# Esp32_Shield_V3_no_LED.net
KiCad netlist of a schematic drawn in EAGLE
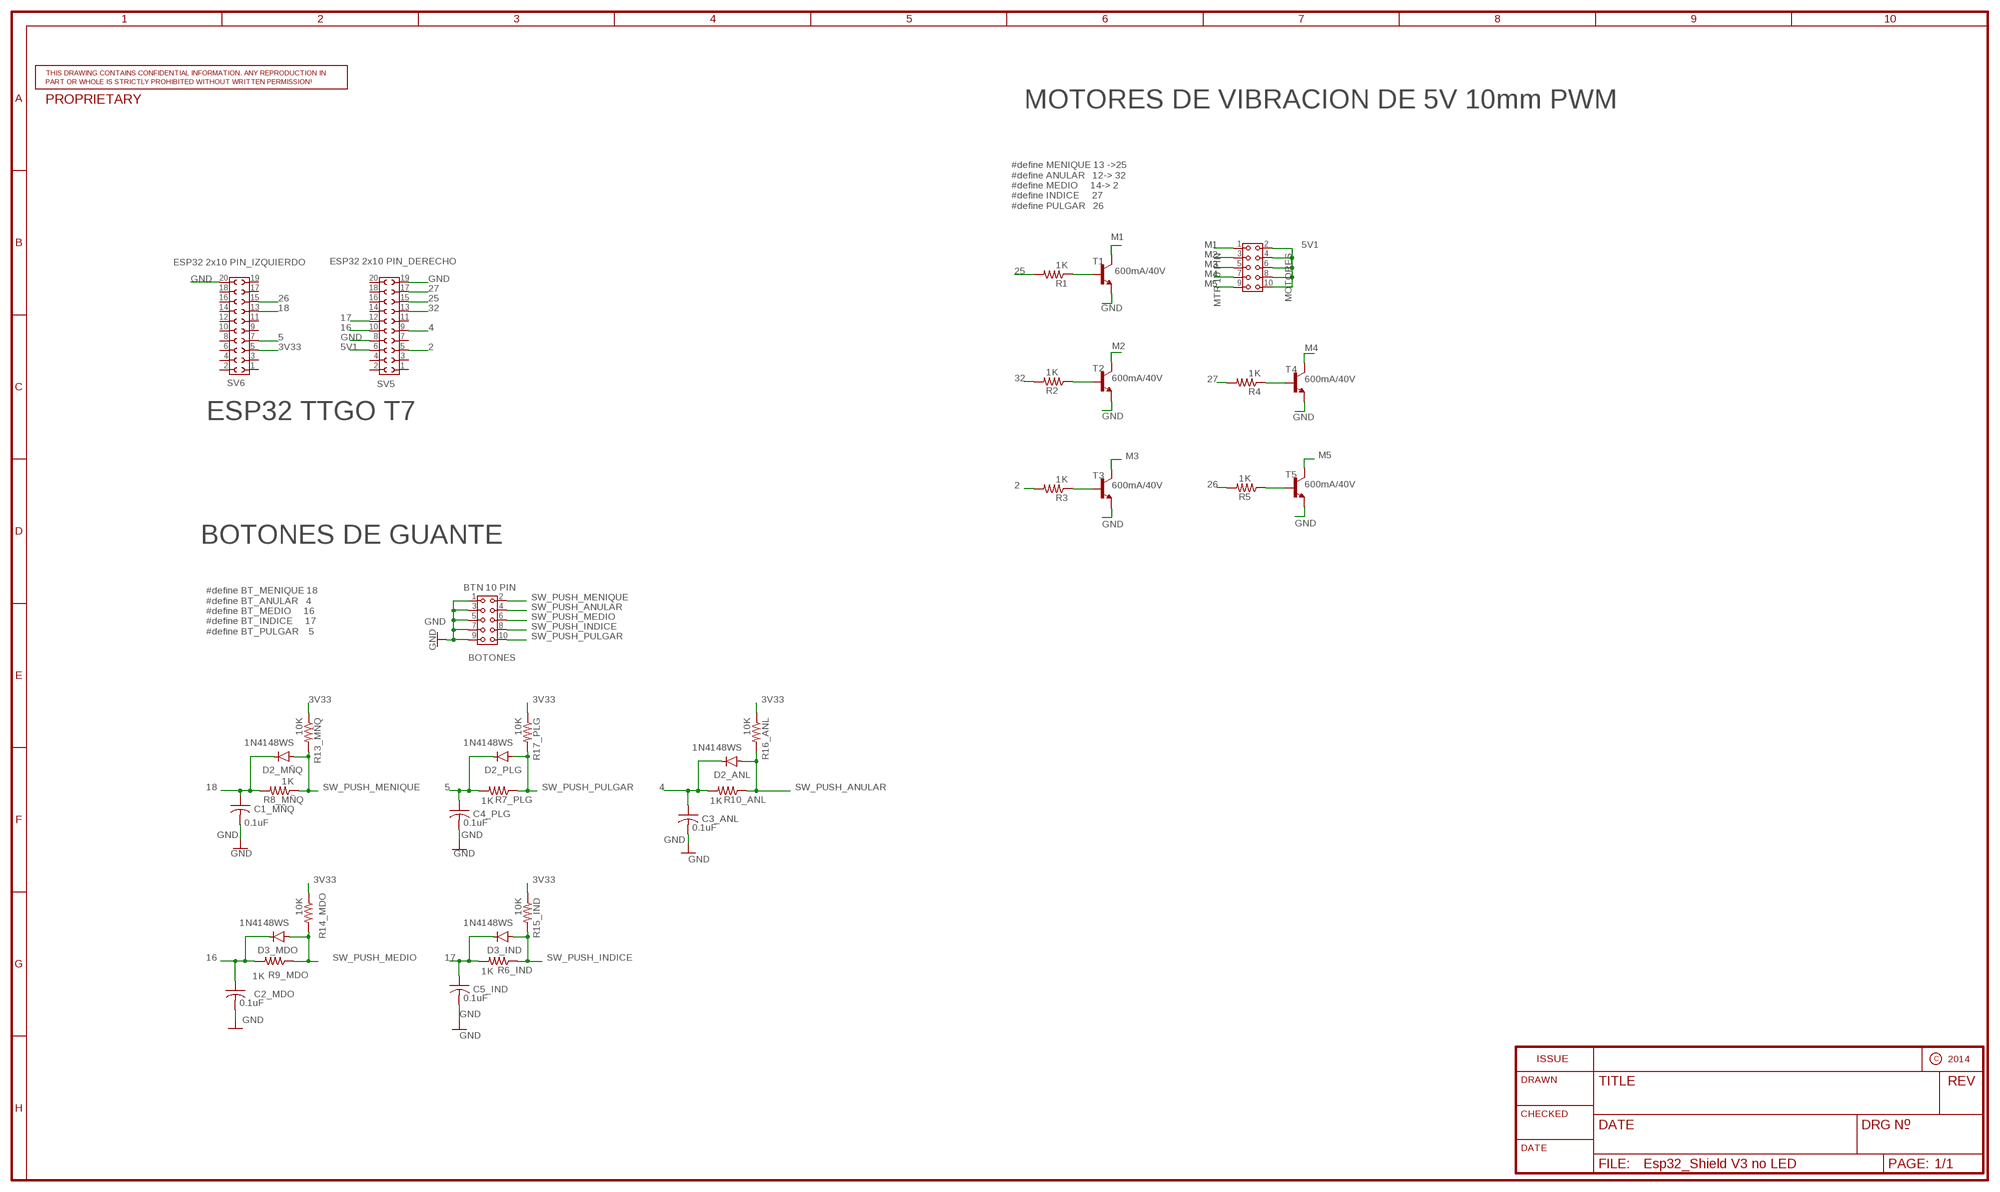
[diagram p0: schematic, sheet 1]

(export (version "E")
  (design (tool "Eeschema 10.0.6"))
  (components
    (comp (ref "BOTONES")
      (value "BTN 10 PIN")
      (footprint "eagle-import:61301021821")
      (libsource (lib "eagle-import") (part "6130XX21821_61301021821"))
    )
    (comp (ref "C1_MÑQ")
      (value "0.1uF")
      (footprint "eagle-import:C0805")
      (libsource (lib "eagle-import") (part "C-USC0805"))
    )
    (comp (ref "C2_MDO")
      (value "0.1uF")
      (footprint "eagle-import:C0805")
      (libsource (lib "eagle-import") (part "C-USC0805"))
    )
    (comp (ref "C3_ANL")
      (value "0.1uF")
      (footprint "eagle-import:C0805")
      (libsource (lib "eagle-import") (part "C-USC0805"))
    )
    (comp (ref "C4_PLG")
      (value "0.1uF")
      (footprint "eagle-import:C0805")
      (libsource (lib "eagle-import") (part "C-USC0805"))
    )
    (comp (ref "C5_IND")
      (value "0.1uF")
      (footprint "eagle-import:C0805")
      (libsource (lib "eagle-import") (part "C-USC0805"))
    )
    (comp (ref "D2_ANL")
      (value "1N4148WS")
      (footprint "eagle-import:SOD-323")
      (fields
        (field (name "DIGIKEY_PART_NUMBER") "1N4148WSFSTR-ND")
        (field (name "MANUFACTURER") "Diodes Incorporated")
        (field (name "CREATED_BY") "PCBLayout.com")
      )
      (libsource (lib "eagle-import") (part "1N4148WS"))
    )
    (comp (ref "D2_MÑQ")
      (value "1N4148WS")
      (footprint "eagle-import:SOD-323")
      (fields
        (field (name "DIGIKEY_PART_NUMBER") "1N4148WSFSTR-ND")
        (field (name "MANUFACTURER") "Diodes Incorporated")
        (field (name "CREATED_BY") "PCBLayout.com")
      )
      (libsource (lib "eagle-import") (part "1N4148WS"))
    )
    (comp (ref "D2_PLG")
      (value "1N4148WS")
      (footprint "eagle-import:SOD-323")
      (fields
        (field (name "DIGIKEY_PART_NUMBER") "1N4148WSFSTR-ND")
        (field (name "MANUFACTURER") "Diodes Incorporated")
        (field (name "CREATED_BY") "PCBLayout.com")
      )
      (libsource (lib "eagle-import") (part "1N4148WS"))
    )
    (comp (ref "D3_IND")
      (value "1N4148WS")
      (footprint "eagle-import:SOD-323")
      (fields
        (field (name "DIGIKEY_PART_NUMBER") "1N4148WSFSTR-ND")
        (field (name "MANUFACTURER") "Diodes Incorporated")
        (field (name "CREATED_BY") "PCBLayout.com")
      )
      (libsource (lib "eagle-import") (part "1N4148WS"))
    )
    (comp (ref "D3_MDO")
      (value "1N4148WS")
      (footprint "eagle-import:SOD-323")
      (fields
        (field (name "DIGIKEY_PART_NUMBER") "1N4148WSFSTR-ND")
        (field (name "MANUFACTURER") "Diodes Incorporated")
        (field (name "CREATED_BY") "PCBLayout.com")
      )
      (libsource (lib "eagle-import") (part "1N4148WS"))
    )
    (comp (ref "MOTORES")
      (value "MTR 10 PIN")
      (footprint "eagle-import:61301021821")
      (libsource (lib "eagle-import") (part "6130XX21821_61301021821"))
    )
    (comp (ref "R1")
      (value "1K")
      (footprint "eagle-import:R0805")
      (libsource (lib "eagle-import") (part "R-US_R0805"))
    )
    (comp (ref "R2")
      (value "1K")
      (footprint "eagle-import:R0805")
      (libsource (lib "eagle-import") (part "R-US_R0805"))
    )
    (comp (ref "R3")
      (value "1K")
      (footprint "eagle-import:R0805")
      (libsource (lib "eagle-import") (part "R-US_R0805"))
    )
    (comp (ref "R4")
      (value "1K")
      (footprint "eagle-import:R0805")
      (libsource (lib "eagle-import") (part "R-US_R0805"))
    )
    (comp (ref "R5")
      (value "1K")
      (footprint "eagle-import:R0805")
      (libsource (lib "eagle-import") (part "R-US_R0805"))
    )
    (comp (ref "R6_IND")
      (value "1K")
      (footprint "eagle-import:R0805")
      (libsource (lib "eagle-import") (part "R-US_R0805"))
    )
    (comp (ref "R7_PLG")
      (value "1K")
      (footprint "eagle-import:R0805")
      (libsource (lib "eagle-import") (part "R-US_R0805"))
    )
    (comp (ref "R8_MÑQ")
      (value "1K")
      (footprint "eagle-import:R0805")
      (libsource (lib "eagle-import") (part "R-US_R0805"))
    )
    (comp (ref "R9_MDO")
      (value "1K")
      (footprint "eagle-import:R0805")
      (libsource (lib "eagle-import") (part "R-US_R0805"))
    )
    (comp (ref "R10_ANL")
      (value "1K")
      (footprint "eagle-import:R0805")
      (libsource (lib "eagle-import") (part "R-US_R0805"))
    )
    (comp (ref "R13_MÑQ")
      (value "10K")
      (footprint "eagle-import:R0805")
      (libsource (lib "eagle-import") (part "R-US_R0805"))
    )
    (comp (ref "R14_MDO")
      (value "10K")
      (footprint "eagle-import:R0805")
      (libsource (lib "eagle-import") (part "R-US_R0805"))
    )
    (comp (ref "R15_IND")
      (value "10K")
      (footprint "eagle-import:R0805")
      (libsource (lib "eagle-import") (part "R-US_R0805"))
    )
    (comp (ref "R16_ANL")
      (value "10K")
      (footprint "eagle-import:R0805")
      (libsource (lib "eagle-import") (part "R-US_R0805"))
    )
    (comp (ref "R17_PLG")
      (value "10K")
      (footprint "eagle-import:R0805")
      (libsource (lib "eagle-import") (part "R-US_R0805"))
    )
    (comp (ref "SV5")
      (value "ESP32 2x10 PIN_DERECHO")
      (footprint "eagle-import:61302021821")
      (libsource (lib "eagle-import") (part "6130XX21821_61302021821"))
    )
    (comp (ref "SV6")
      (value "ESP32 2x10 PIN_IZQUIERDO")
      (footprint "eagle-import:61302021821")
      (libsource (lib "eagle-import") (part "6130XX21821_61302021821"))
    )
    (comp (ref "T1")
      (value "600mA/40V")
      (footprint "eagle-import:SOT23-3")
      (libsource (lib "eagle-import") (part "TRANS_NPN-MMBT2222AL"))
    )
    (comp (ref "T2")
      (value "600mA/40V")
      (footprint "eagle-import:SOT23-3")
      (libsource (lib "eagle-import") (part "TRANS_NPN-MMBT2222AL"))
    )
    (comp (ref "T3")
      (value "600mA/40V")
      (footprint "eagle-import:SOT23-3")
      (libsource (lib "eagle-import") (part "TRANS_NPN-MMBT2222AL"))
    )
    (comp (ref "T4")
      (value "600mA/40V")
      (footprint "eagle-import:SOT23-3")
      (libsource (lib "eagle-import") (part "TRANS_NPN-MMBT2222AL"))
    )
    (comp (ref "T5")
      (value "600mA/40V")
      (footprint "eagle-import:SOT23-3")
      (libsource (lib "eagle-import") (part "TRANS_NPN-MMBT2222AL"))
    )
  )
  (nets
    (net (code "1") (name "/2") (class "Default")
      (node (ref "R3") (pin "2") (pinfunction "2_2") (pintype "passive"))
      (node (ref "SV5") (pin "5") (pinfunction "5_5") (pintype "passive"))
    )
    (net (code "2") (name "/3V33") (class "Default")
      (node (ref "R13_MÑQ") (pin "1") (pinfunction "1_1") (pintype "passive"))
      (node (ref "R14_MDO") (pin "1") (pinfunction "1_1") (pintype "passive"))
      (node (ref "R15_IND") (pin "1") (pinfunction "1_1") (pintype "passive"))
      (node (ref "R16_ANL") (pin "1") (pinfunction "1_1") (pintype "passive"))
      (node (ref "R17_PLG") (pin "1") (pinfunction "1_1") (pintype "passive"))
      (node (ref "SV6") (pin "5") (pinfunction "5_5") (pintype "passive"))
    )
    (net (code "3") (name "/4") (class "Default")
      (node (ref "C3_ANL") (pin "1") (pinfunction "1_1") (pintype "passive"))
      (node (ref "D2_ANL") (pin "C") (pinfunction "C_C") (pintype "passive"))
      (node (ref "R10_ANL") (pin "2") (pinfunction "2_2") (pintype "passive"))
      (node (ref "SV5") (pin "9") (pinfunction "9_9") (pintype "passive"))
    )
    (net (code "4") (name "/5") (class "Default")
      (node (ref "C4_PLG") (pin "1") (pinfunction "1_1") (pintype "passive"))
      (node (ref "D2_PLG") (pin "C") (pinfunction "C_C") (pintype "passive"))
      (node (ref "R7_PLG") (pin "2") (pinfunction "2_2") (pintype "passive"))
      (node (ref "SV6") (pin "7") (pinfunction "7_7") (pintype "passive"))
    )
    (net (code "5") (name "/5V1") (class "Default")
      (node (ref "MOTORES") (pin "10") (pinfunction "10_10") (pintype "passive"))
      (node (ref "MOTORES") (pin "2") (pinfunction "2_2") (pintype "passive"))
      (node (ref "MOTORES") (pin "4") (pinfunction "4_4") (pintype "passive"))
      (node (ref "MOTORES") (pin "6") (pinfunction "6_6") (pintype "passive"))
      (node (ref "MOTORES") (pin "8") (pinfunction "8_8") (pintype "passive"))
      (node (ref "SV5") (pin "6") (pinfunction "6_6") (pintype "passive"))
    )
    (net (code "6") (name "/16") (class "Default")
      (node (ref "C2_MDO") (pin "1") (pinfunction "1_1") (pintype "passive"))
      (node (ref "D3_MDO") (pin "C") (pinfunction "C_C") (pintype "passive"))
      (node (ref "R9_MDO") (pin "2") (pinfunction "2_2") (pintype "passive"))
      (node (ref "SV5") (pin "10") (pinfunction "10_10") (pintype "passive"))
    )
    (net (code "7") (name "/17") (class "Default")
      (node (ref "C5_IND") (pin "1") (pinfunction "1_1") (pintype "passive"))
      (node (ref "D3_IND") (pin "C") (pinfunction "C_C") (pintype "passive"))
      (node (ref "R6_IND") (pin "2") (pinfunction "2_2") (pintype "passive"))
      (node (ref "SV5") (pin "12") (pinfunction "12_12") (pintype "passive"))
    )
    (net (code "8") (name "/18") (class "Default")
      (node (ref "C1_MÑQ") (pin "1") (pinfunction "1_1") (pintype "passive"))
      (node (ref "D2_MÑQ") (pin "C") (pinfunction "C_C") (pintype "passive"))
      (node (ref "R8_MÑQ") (pin "2") (pinfunction "2_2") (pintype "passive"))
      (node (ref "SV6") (pin "13") (pinfunction "13_13") (pintype "passive"))
    )
    (net (code "9") (name "/25") (class "Default")
      (node (ref "R1") (pin "2") (pinfunction "2_2") (pintype "passive"))
      (node (ref "SV5") (pin "15") (pinfunction "15_15") (pintype "passive"))
    )
    (net (code "10") (name "/26") (class "Default")
      (node (ref "R5") (pin "2") (pinfunction "2_2") (pintype "passive"))
      (node (ref "SV6") (pin "15") (pinfunction "15_15") (pintype "passive"))
    )
    (net (code "11") (name "/27") (class "Default")
      (node (ref "R4") (pin "2") (pinfunction "2_2") (pintype "passive"))
      (node (ref "SV5") (pin "17") (pinfunction "17_17") (pintype "passive"))
    )
    (net (code "12") (name "/32") (class "Default")
      (node (ref "R2") (pin "2") (pinfunction "2_2") (pintype "passive"))
      (node (ref "SV5") (pin "13") (pinfunction "13_13") (pintype "passive"))
    )
    (net (code "13") (name "/M1") (class "Default")
      (node (ref "MOTORES") (pin "1") (pinfunction "1_1") (pintype "passive"))
      (node (ref "T1") (pin "3") (pinfunction "C_3") (pintype "passive"))
    )
    (net (code "14") (name "/M2") (class "Default")
      (node (ref "MOTORES") (pin "3") (pinfunction "3_3") (pintype "passive"))
      (node (ref "T2") (pin "3") (pinfunction "C_3") (pintype "passive"))
    )
    (net (code "15") (name "/M3") (class "Default")
      (node (ref "MOTORES") (pin "5") (pinfunction "5_5") (pintype "passive"))
      (node (ref "T3") (pin "3") (pinfunction "C_3") (pintype "passive"))
    )
    (net (code "16") (name "/M4") (class "Default")
      (node (ref "MOTORES") (pin "7") (pinfunction "7_7") (pintype "passive"))
      (node (ref "T4") (pin "3") (pinfunction "C_3") (pintype "passive"))
    )
    (net (code "17") (name "/M5") (class "Default")
      (node (ref "MOTORES") (pin "9") (pinfunction "9_9") (pintype "passive"))
      (node (ref "T5") (pin "3") (pinfunction "C_3") (pintype "passive"))
    )
    (net (code "18") (name "/SW_PUSH_ANULAR") (class "Default")
      (node (ref "BOTONES") (pin "4") (pinfunction "4_4") (pintype "passive"))
      (node (ref "D2_ANL") (pin "A") (pinfunction "A_A") (pintype "passive"))
      (node (ref "R10_ANL") (pin "1") (pinfunction "1_1") (pintype "passive"))
      (node (ref "R16_ANL") (pin "2") (pinfunction "2_2") (pintype "passive"))
    )
    (net (code "19") (name "/SW_PUSH_INDICE") (class "Default")
      (node (ref "BOTONES") (pin "8") (pinfunction "8_8") (pintype "passive"))
      (node (ref "D3_IND") (pin "A") (pinfunction "A_A") (pintype "passive"))
      (node (ref "R15_IND") (pin "2") (pinfunction "2_2") (pintype "passive"))
      (node (ref "R6_IND") (pin "1") (pinfunction "1_1") (pintype "passive"))
    )
    (net (code "20") (name "/SW_PUSH_MEDIO") (class "Default")
      (node (ref "BOTONES") (pin "6") (pinfunction "6_6") (pintype "passive"))
      (node (ref "D3_MDO") (pin "A") (pinfunction "A_A") (pintype "passive"))
      (node (ref "R14_MDO") (pin "2") (pinfunction "2_2") (pintype "passive"))
      (node (ref "R9_MDO") (pin "1") (pinfunction "1_1") (pintype "passive"))
    )
    (net (code "21") (name "/SW_PUSH_MENIQUE") (class "Default")
      (node (ref "BOTONES") (pin "2") (pinfunction "2_2") (pintype "passive"))
      (node (ref "D2_MÑQ") (pin "A") (pinfunction "A_A") (pintype "passive"))
      (node (ref "R13_MÑQ") (pin "2") (pinfunction "2_2") (pintype "passive"))
      (node (ref "R8_MÑQ") (pin "1") (pinfunction "1_1") (pintype "passive"))
    )
    (net (code "22") (name "/SW_PUSH_PULGAR") (class "Default")
      (node (ref "BOTONES") (pin "10") (pinfunction "10_10") (pintype "passive"))
      (node (ref "D2_PLG") (pin "A") (pinfunction "A_A") (pintype "passive"))
      (node (ref "R17_PLG") (pin "2") (pinfunction "2_2") (pintype "passive"))
      (node (ref "R7_PLG") (pin "1") (pinfunction "1_1") (pintype "passive"))
    )
    (net (code "23") (name "GND") (class "Default")
      (node (ref "BOTONES") (pin "1") (pinfunction "1_1") (pintype "passive"))
      (node (ref "BOTONES") (pin "3") (pinfunction "3_3") (pintype "passive"))
      (node (ref "BOTONES") (pin "5") (pinfunction "5_5") (pintype "passive"))
      (node (ref "BOTONES") (pin "7") (pinfunction "7_7") (pintype "passive"))
      (node (ref "BOTONES") (pin "9") (pinfunction "9_9") (pintype "passive"))
      (node (ref "C1_MÑQ") (pin "2") (pinfunction "2_2") (pintype "passive"))
      (node (ref "C2_MDO") (pin "2") (pinfunction "2_2") (pintype "passive"))
      (node (ref "C3_ANL") (pin "2") (pinfunction "2_2") (pintype "passive"))
      (node (ref "C4_PLG") (pin "2") (pinfunction "2_2") (pintype "passive"))
      (node (ref "C5_IND") (pin "2") (pinfunction "2_2") (pintype "passive"))
      (node (ref "SV5") (pin "19") (pinfunction "19_19") (pintype "passive"))
      (node (ref "SV5") (pin "8") (pinfunction "8_8") (pintype "passive"))
      (node (ref "SV6") (pin "20") (pinfunction "20_20") (pintype "passive"))
      (node (ref "T1") (pin "2") (pinfunction "E_2") (pintype "passive"))
      (node (ref "T2") (pin "2") (pinfunction "E_2") (pintype "passive"))
      (node (ref "T3") (pin "2") (pinfunction "E_2") (pintype "passive"))
      (node (ref "T4") (pin "2") (pinfunction "E_2") (pintype "passive"))
      (node (ref "T5") (pin "2") (pinfunction "E_2") (pintype "passive"))
    )
    (net (code "24") (name "Net-(T1-B)") (class "Default")
      (node (ref "R1") (pin "1") (pinfunction "1_1") (pintype "passive"))
      (node (ref "T1") (pin "1") (pinfunction "B_1") (pintype "passive"))
    )
    (net (code "25") (name "Net-(T2-B)") (class "Default")
      (node (ref "R2") (pin "1") (pinfunction "1_1") (pintype "passive"))
      (node (ref "T2") (pin "1") (pinfunction "B_1") (pintype "passive"))
    )
    (net (code "26") (name "Net-(T3-B)") (class "Default")
      (node (ref "R3") (pin "1") (pinfunction "1_1") (pintype "passive"))
      (node (ref "T3") (pin "1") (pinfunction "B_1") (pintype "passive"))
    )
    (net (code "27") (name "Net-(T4-B)") (class "Default")
      (node (ref "R4") (pin "1") (pinfunction "1_1") (pintype "passive"))
      (node (ref "T4") (pin "1") (pinfunction "B_1") (pintype "passive"))
    )
    (net (code "28") (name "Net-(T5-B)") (class "Default")
      (node (ref "R5") (pin "1") (pinfunction "1_1") (pintype "passive"))
      (node (ref "T5") (pin "1") (pinfunction "B_1") (pintype "passive"))
    )
    (net (code "29") (name "unconnected-(SV5-Pad1)") (class "Default")
      (node (ref "SV5") (pin "1") (pinfunction "1_1") (pintype "passive"))
    )
    (net (code "30") (name "unconnected-(SV5-Pad2)") (class "Default")
      (node (ref "SV5") (pin "2") (pinfunction "2_2") (pintype "passive"))
    )
    (net (code "31") (name "unconnected-(SV5-Pad3)") (class "Default")
      (node (ref "SV5") (pin "3") (pinfunction "3_3") (pintype "passive"))
    )
    (net (code "32") (name "unconnected-(SV5-Pad4)") (class "Default")
      (node (ref "SV5") (pin "4") (pinfunction "4_4") (pintype "passive"))
    )
    (net (code "33") (name "unconnected-(SV5-Pad7)") (class "Default")
      (node (ref "SV5") (pin "7") (pinfunction "7_7") (pintype "passive"))
    )
    (net (code "34") (name "unconnected-(SV5-Pad11)") (class "Default")
      (node (ref "SV5") (pin "11") (pinfunction "11_11") (pintype "passive"))
    )
    (net (code "35") (name "unconnected-(SV5-Pad14)") (class "Default")
      (node (ref "SV5") (pin "14") (pinfunction "14_14") (pintype "passive"))
    )
    (net (code "36") (name "unconnected-(SV5-Pad16)") (class "Default")
      (node (ref "SV5") (pin "16") (pinfunction "16_16") (pintype "passive"))
    )
    (net (code "37") (name "unconnected-(SV5-Pad18)") (class "Default")
      (node (ref "SV5") (pin "18") (pinfunction "18_18") (pintype "passive"))
    )
    (net (code "38") (name "unconnected-(SV5-Pad20)") (class "Default")
      (node (ref "SV5") (pin "20") (pinfunction "20_20") (pintype "passive"))
    )
    (net (code "39") (name "unconnected-(SV6-Pad1)") (class "Default")
      (node (ref "SV6") (pin "1") (pinfunction "1_1") (pintype "passive"))
    )
    (net (code "40") (name "unconnected-(SV6-Pad2)") (class "Default")
      (node (ref "SV6") (pin "2") (pinfunction "2_2") (pintype "passive"))
    )
    (net (code "41") (name "unconnected-(SV6-Pad3)") (class "Default")
      (node (ref "SV6") (pin "3") (pinfunction "3_3") (pintype "passive"))
    )
    (net (code "42") (name "unconnected-(SV6-Pad4)") (class "Default")
      (node (ref "SV6") (pin "4") (pinfunction "4_4") (pintype "passive"))
    )
    (net (code "43") (name "unconnected-(SV6-Pad6)") (class "Default")
      (node (ref "SV6") (pin "6") (pinfunction "6_6") (pintype "passive"))
    )
    (net (code "44") (name "unconnected-(SV6-Pad8)") (class "Default")
      (node (ref "SV6") (pin "8") (pinfunction "8_8") (pintype "passive"))
    )
    (net (code "45") (name "unconnected-(SV6-Pad9)") (class "Default")
      (node (ref "SV6") (pin "9") (pinfunction "9_9") (pintype "passive"))
    )
    (net (code "46") (name "unconnected-(SV6-Pad10)") (class "Default")
      (node (ref "SV6") (pin "10") (pinfunction "10_10") (pintype "passive"))
    )
    (net (code "47") (name "unconnected-(SV6-Pad11)") (class "Default")
      (node (ref "SV6") (pin "11") (pinfunction "11_11") (pintype "passive"))
    )
    (net (code "48") (name "unconnected-(SV6-Pad12)") (class "Default")
      (node (ref "SV6") (pin "12") (pinfunction "12_12") (pintype "passive"))
    )
    (net (code "49") (name "unconnected-(SV6-Pad14)") (class "Default")
      (node (ref "SV6") (pin "14") (pinfunction "14_14") (pintype "passive"))
    )
    (net (code "50") (name "unconnected-(SV6-Pad16)") (class "Default")
      (node (ref "SV6") (pin "16") (pinfunction "16_16") (pintype "passive"))
    )
    (net (code "51") (name "unconnected-(SV6-Pad17)") (class "Default")
      (node (ref "SV6") (pin "17") (pinfunction "17_17") (pintype "passive"))
    )
    (net (code "52") (name "unconnected-(SV6-Pad18)") (class "Default")
      (node (ref "SV6") (pin "18") (pinfunction "18_18") (pintype "passive"))
    )
    (net (code "53") (name "unconnected-(SV6-Pad19)") (class "Default")
      (node (ref "SV6") (pin "19") (pinfunction "19_19") (pintype "passive"))
    )
  )
)
